# PLD_Flash-Memory.net
KiCad netlist of a schematic drawn in Altium Designer
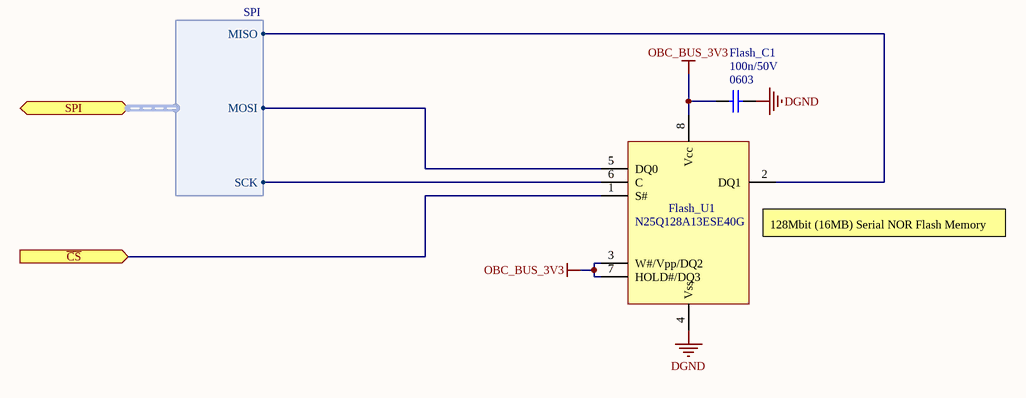
[diagram p0: PLD_Flash-Memory.SchDoc]

(export (version "E")
  (design (tool "Eeschema 10.0.6"))
  (components
    (comp (ref "Flash_C1")
      (value "100n/50V")
      (footprint "SMD_Capacitor_0603")
      (description "Ceramic Cap Kemet COTS 100n/50V X7R 0603")
      (fields
        (field (name "MANUFACTURER") "Kemet")
        (field (name "MANUFACTURERPARTNUMBER") "C0603T104K5RALTU")
        (field (name "PACKAGE") "0603")
      )
      (libsource (lib "capacitors") (part "Cer_C0603T104K5RALTU"))
    )
    (comp (ref "Flash_U1")
      (value "~")
      (footprint "SOIC-8-W")
      (description "128Mbit, 3V Serial NOR Flash Memory")
      (fields
        (field (name "MANUFACTURER") "Micron")
        (field (name "MANUFACTURERPARTNUMBER") "N25Q128A13ESE40G")
      )
      (libsource (lib "microcircuits") (part "N25Q128A13ESE40G"))
    )
  )
  (nets
    (net (code "2") (name "/MISO") (class "Default")
      (node (ref "Flash_U1") (pin "2") (pinfunction "DQ1_2") (pintype "passive"))
    )
    (net (code "3") (name "/MOSI") (class "Default")
      (node (ref "Flash_U1") (pin "5") (pinfunction "DQ0_5") (pintype "passive"))
    )
    (net (code "4") (name "/SCK") (class "Default")
      (node (ref "Flash_U1") (pin "6") (pinfunction "C_6") (pintype "passive"))
    )
    (net (code "6") (name "/~{CS}") (class "Default")
      (node (ref "Flash_U1") (pin "1") (pinfunction "S#_1") (pintype "passive"))
    )
    (net (code "7") (name "DGND") (class "Default")
      (node (ref "Flash_C1") (pin "1") (pinfunction "1_1") (pintype "passive"))
      (node (ref "Flash_U1") (pin "4") (pinfunction "Vss_4") (pintype "passive"))
    )
    (net (code "8") (name "OBC_BUS_3V3") (class "Default")
      (node (ref "Flash_C1") (pin "2") (pinfunction "2_2") (pintype "passive"))
      (node (ref "Flash_U1") (pin "3") (pinfunction "W#/Vpp/DQ2_3") (pintype "passive"))
      (node (ref "Flash_U1") (pin "7") (pinfunction "HOLD#/DQ3_7") (pintype "passive"))
      (node (ref "Flash_U1") (pin "8") (pinfunction "Vcc_8") (pintype "passive"))
    )
  )
)
